# Cookie_Filter.net
KiCad netlist of a schematic drawn in EAGLE
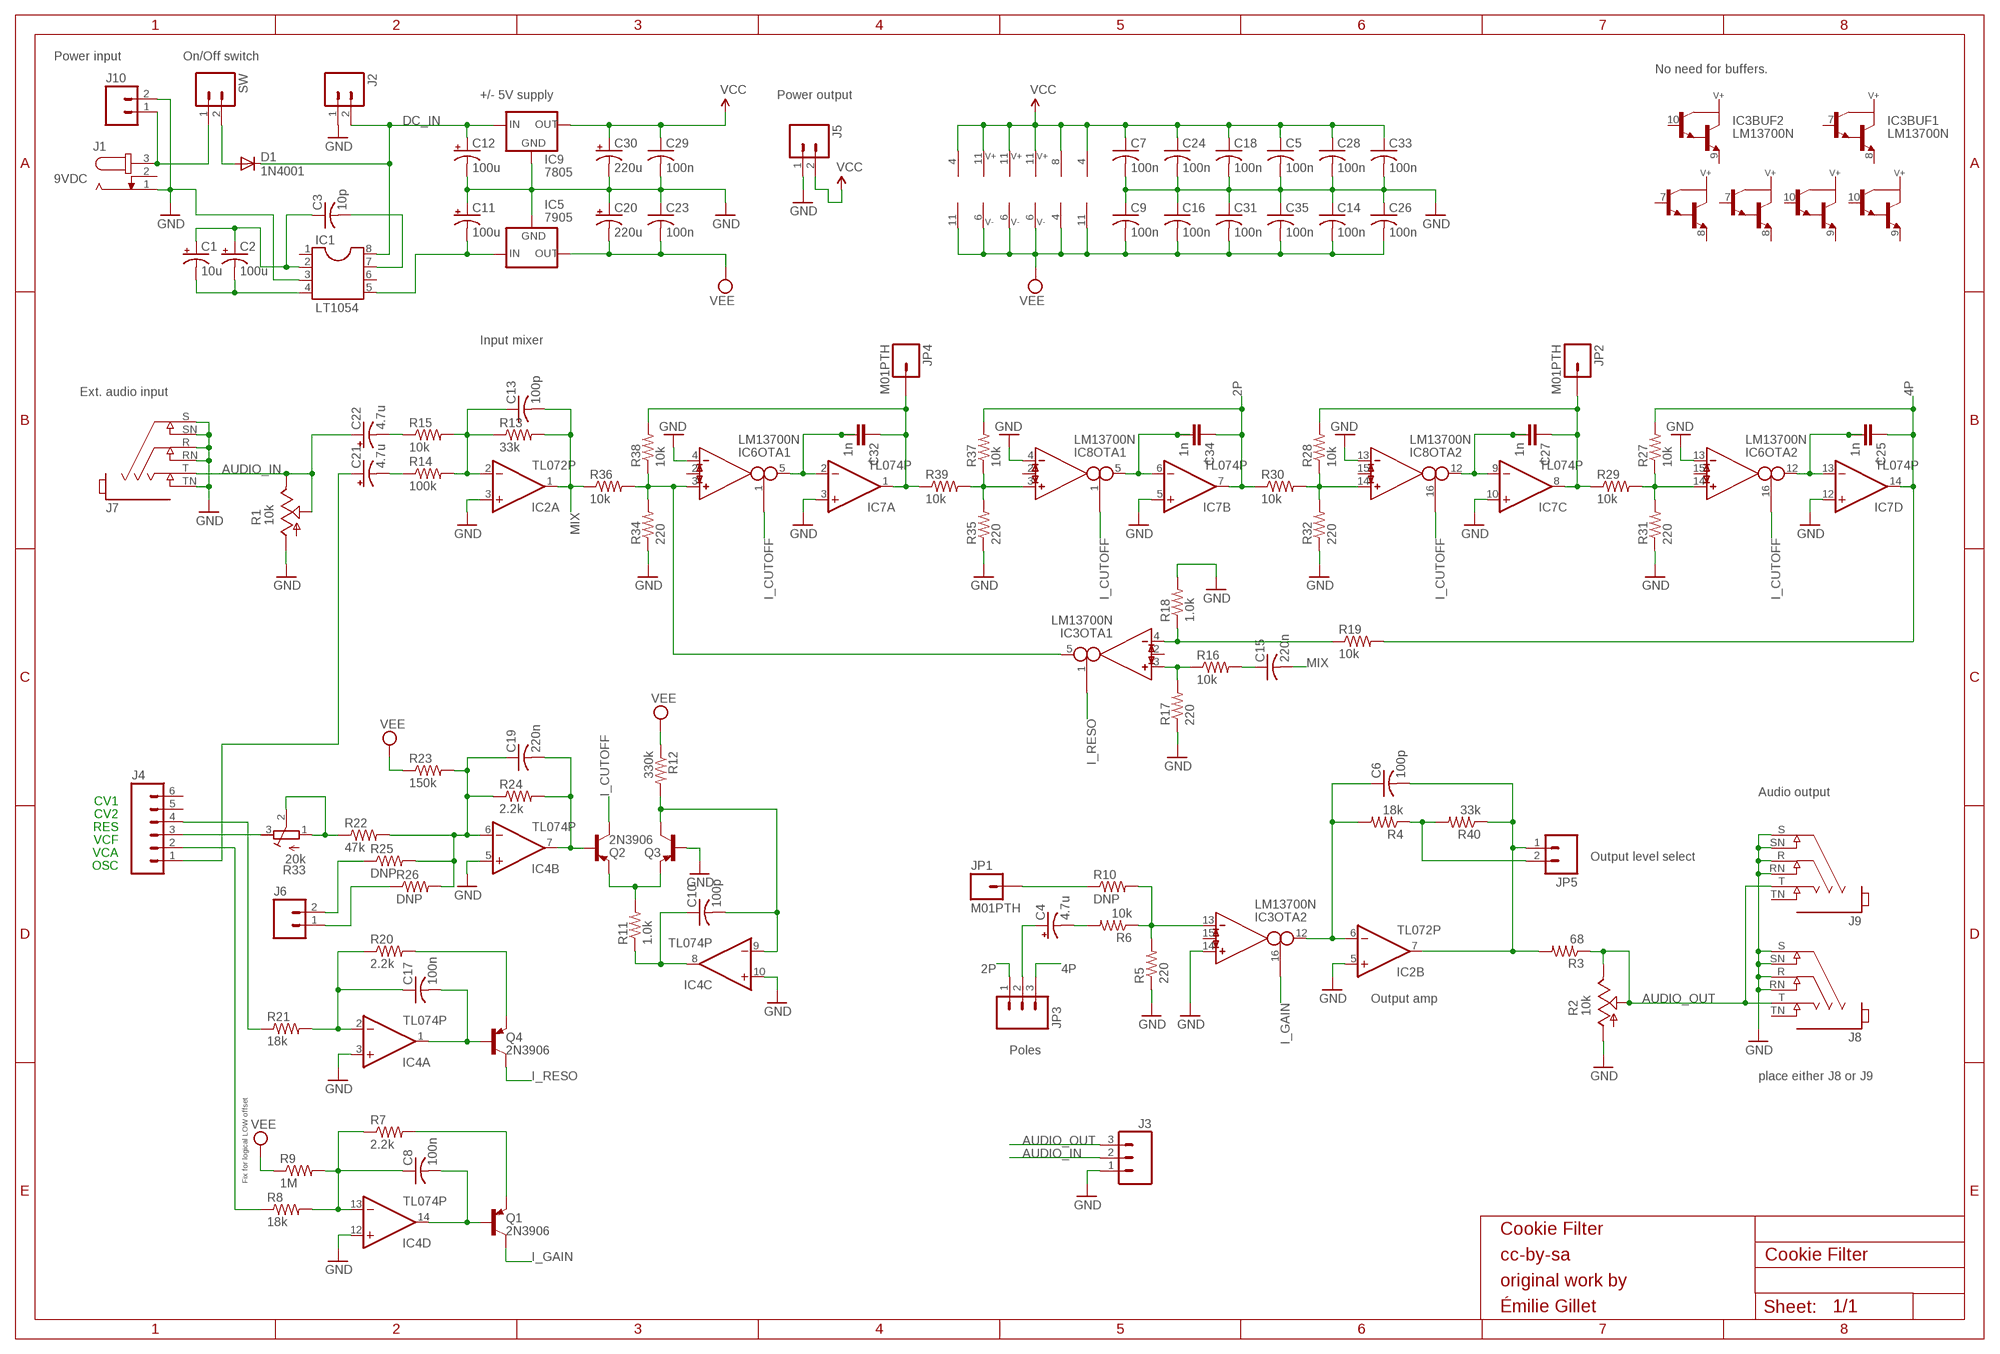
[diagram p0: schematic, sheet 1]

(export (version "E")
  (design (tool "Eeschema 10.0.6"))
  (components
    (comp (ref "C1")
      (value "10u")
      (footprint "eagle-import:E2,5-5")
      (libsource (lib "eagle-import") (part "CPOL-USE2.5-5"))
    )
    (comp (ref "C2")
      (value "100u")
      (footprint "eagle-import:E2,5-6")
      (libsource (lib "eagle-import") (part "CPOL-USE2.5-6"))
    )
    (comp (ref "C3")
      (value "10p")
      (footprint "eagle-import:C025-025X050")
      (libsource (lib "eagle-import") (part "C-US025-025X050"))
    )
    (comp (ref "C4")
      (value "4.7u")
      (footprint "eagle-import:E2,5-6")
      (libsource (lib "eagle-import") (part "CPOL-USE2.5-6"))
    )
    (comp (ref "C5")
      (value "100n")
      (footprint "eagle-import:C025-025X050")
      (libsource (lib "eagle-import") (part "C-US025-025X050"))
    )
    (comp (ref "C6")
      (value "100p")
      (footprint "eagle-import:C025-025X050")
      (libsource (lib "eagle-import") (part "C-US025-025X050"))
    )
    (comp (ref "C7")
      (value "100n")
      (footprint "eagle-import:C025-025X050")
      (libsource (lib "eagle-import") (part "C-US025-025X050"))
    )
    (comp (ref "C8")
      (value "100n")
      (footprint "eagle-import:C025-025X050")
      (libsource (lib "eagle-import") (part "C-US025-025X050"))
    )
    (comp (ref "C9")
      (value "100n")
      (footprint "eagle-import:C025-025X050")
      (libsource (lib "eagle-import") (part "C-US025-025X050"))
    )
    (comp (ref "C10")
      (value "100p")
      (footprint "eagle-import:C025-025X050")
      (libsource (lib "eagle-import") (part "C-US025-025X050"))
    )
    (comp (ref "C11")
      (value "100u")
      (footprint "eagle-import:E2,5-6")
      (libsource (lib "eagle-import") (part "CPOL-USE2.5-6"))
    )
    (comp (ref "C12")
      (value "100u")
      (footprint "eagle-import:E2,5-6")
      (libsource (lib "eagle-import") (part "CPOL-USE2.5-6"))
    )
    (comp (ref "C13")
      (value "100p")
      (footprint "eagle-import:C025-025X050")
      (libsource (lib "eagle-import") (part "C-US025-025X050"))
    )
    (comp (ref "C14")
      (value "100n")
      (footprint "eagle-import:C025-025X050")
      (libsource (lib "eagle-import") (part "C-US025-025X050"))
    )
    (comp (ref "C15")
      (value "220n")
      (footprint "eagle-import:C025-025X050")
      (libsource (lib "eagle-import") (part "C-US025-025X050"))
    )
    (comp (ref "C16")
      (value "100n")
      (footprint "eagle-import:C025-025X050")
      (libsource (lib "eagle-import") (part "C-US025-025X050"))
    )
    (comp (ref "C17")
      (value "100n")
      (footprint "eagle-import:C025-025X050")
      (libsource (lib "eagle-import") (part "C-US025-025X050"))
    )
    (comp (ref "C18")
      (value "100n")
      (footprint "eagle-import:C025-025X050")
      (libsource (lib "eagle-import") (part "C-US025-025X050"))
    )
    (comp (ref "C19")
      (value "220n")
      (footprint "eagle-import:C025-025X050")
      (libsource (lib "eagle-import") (part "C-US025-025X050"))
    )
    (comp (ref "C20")
      (value "220u")
      (footprint "eagle-import:E2,5-7")
      (libsource (lib "eagle-import") (part "CPOL-USE2.5-7"))
    )
    (comp (ref "C21")
      (value "4.7u")
      (footprint "eagle-import:E2,5-6")
      (libsource (lib "eagle-import") (part "CPOL-USE2.5-6"))
    )
    (comp (ref "C22")
      (value "4.7u")
      (footprint "eagle-import:E2,5-6")
      (libsource (lib "eagle-import") (part "CPOL-USE2.5-6"))
    )
    (comp (ref "C23")
      (value "100n")
      (footprint "eagle-import:C025-025X050")
      (libsource (lib "eagle-import") (part "C-US025-025X050"))
    )
    (comp (ref "C24")
      (value "100n")
      (footprint "eagle-import:C025-025X050")
      (libsource (lib "eagle-import") (part "C-US025-025X050"))
    )
    (comp (ref "C25")
      (value "1n")
      (footprint "eagle-import:C2.5_5-2")
      (libsource (lib "eagle-import") (part "C-2.5-5/2"))
    )
    (comp (ref "C26")
      (value "100n")
      (footprint "eagle-import:C025-025X050")
      (libsource (lib "eagle-import") (part "C-US025-025X050"))
    )
    (comp (ref "C27")
      (value "1n")
      (footprint "eagle-import:C2.5_5-2")
      (libsource (lib "eagle-import") (part "C-2.5-5/2"))
    )
    (comp (ref "C28")
      (value "100n")
      (footprint "eagle-import:C025-025X050")
      (libsource (lib "eagle-import") (part "C-US025-025X050"))
    )
    (comp (ref "C29")
      (value "100n")
      (footprint "eagle-import:C025-025X050")
      (libsource (lib "eagle-import") (part "C-US025-025X050"))
    )
    (comp (ref "C30")
      (value "220u")
      (footprint "eagle-import:E2,5-7")
      (libsource (lib "eagle-import") (part "CPOL-USE2.5-7"))
    )
    (comp (ref "C31")
      (value "100n")
      (footprint "eagle-import:C025-025X050")
      (libsource (lib "eagle-import") (part "C-US025-025X050"))
    )
    (comp (ref "C32")
      (value "1n")
      (footprint "eagle-import:C2.5_5-2")
      (libsource (lib "eagle-import") (part "C-2.5-5/2"))
    )
    (comp (ref "C33")
      (value "100n")
      (footprint "eagle-import:C025-025X050")
      (libsource (lib "eagle-import") (part "C-US025-025X050"))
    )
    (comp (ref "C34")
      (value "1n")
      (footprint "eagle-import:C2.5_5-2")
      (libsource (lib "eagle-import") (part "C-2.5-5/2"))
    )
    (comp (ref "C35")
      (value "100n")
      (footprint "eagle-import:C025-025X050")
      (libsource (lib "eagle-import") (part "C-US025-025X050"))
    )
    (comp (ref "D1")
      (value "1N4001")
      (footprint "eagle-import:DO41-10")
      (libsource (lib "eagle-import") (part "1N4004"))
    )
    (comp (ref "IC1")
      (value "LT1054")
      (footprint "eagle-import:DIL08")
      (libsource (lib "eagle-import") (part "DIL8"))
    )
    (comp (ref "IC2")
      (value "TL072P")
      (footprint "eagle-import:DIL08")
      (libsource (lib "eagle-import") (part "TL072P"))
    )
    (comp (ref "IC3")
      (value "LM13700N")
      (footprint "eagle-import:DIL16")
      (libsource (lib "eagle-import") (part "LM13700N"))
    )
    (comp (ref "IC4")
      (value "TL074P")
      (footprint "eagle-import:DIL14")
      (libsource (lib "eagle-import") (part "TL084P"))
    )
    (comp (ref "IC5")
      (value "7905")
      (footprint "eagle-import:79XXS")
      (libsource (lib "eagle-import") (part "79XXS"))
    )
    (comp (ref "IC6")
      (value "LM13700N")
      (footprint "eagle-import:DIL16")
      (libsource (lib "eagle-import") (part "LM13700N"))
    )
    (comp (ref "IC7")
      (value "TL074P")
      (footprint "eagle-import:DIL14")
      (libsource (lib "eagle-import") (part "TL084P"))
    )
    (comp (ref "IC8")
      (value "LM13700N")
      (footprint "eagle-import:DIL16")
      (libsource (lib "eagle-import") (part "LM13700N"))
    )
    (comp (ref "IC9")
      (value "7805")
      (footprint "eagle-import:78XXS")
      (libsource (lib "eagle-import") (part "78XXS"))
    )
    (comp (ref "J1")
      (value "JACK-PLUG1")
      (footprint "eagle-import:SPC4078")
      (libsource (lib "eagle-import") (part "JACK-PLUG1"))
    )
    (comp (ref "J2")
      (value "M02PTH")
      (footprint "eagle-import:1X02")
      (libsource (lib "eagle-import") (part "M02PTH"))
    )
    (comp (ref "J3")
      (value "M03PTH")
      (footprint "eagle-import:1X03")
      (libsource (lib "eagle-import") (part "M03PTH"))
    )
    (comp (ref "J4")
      (value "M06SIP")
      (footprint "eagle-import:1X06")
      (libsource (lib "eagle-import") (part "M06SIP"))
    )
    (comp (ref "J5")
      (value "M02PTH")
      (footprint "eagle-import:1X02")
      (libsource (lib "eagle-import") (part "M02PTH"))
    )
    (comp (ref "J6")
      (value "M02PTH")
      (footprint "eagle-import:1X02")
      (libsource (lib "eagle-import") (part "M02PTH"))
    )
    (comp (ref "J7")
      (value "NRJ4HF")
      (footprint "eagle-import:NRJ6HF")
      (libsource (lib "eagle-import") (part "NRJ6HF"))
    )
    (comp (ref "J8")
      (value "NRJ4HF")
      (footprint "eagle-import:NRJ6HF")
      (libsource (lib "eagle-import") (part "NRJ6HF"))
    )
    (comp (ref "J9")
      (value "NRJ4HF")
      (footprint "eagle-import:NRJ6HF")
      (libsource (lib "eagle-import") (part "NRJ6HF"))
    )
    (comp (ref "J10")
      (value "M02PTH")
      (footprint "eagle-import:1X02")
      (libsource (lib "eagle-import") (part "M02PTH"))
    )
    (comp (ref "JP1")
      (value "M01PTH")
      (footprint "eagle-import:1X01")
      (libsource (lib "eagle-import") (part "M01PTH"))
    )
    (comp (ref "JP2")
      (value "M01PTH")
      (footprint "eagle-import:1X01")
      (libsource (lib "eagle-import") (part "M01PTH"))
    )
    (comp (ref "JP3")
      (value "M03PTH")
      (footprint "eagle-import:1X03")
      (libsource (lib "eagle-import") (part "M03PTH"))
    )
    (comp (ref "JP4")
      (value "M01PTH")
      (footprint "eagle-import:1X01")
      (libsource (lib "eagle-import") (part "M01PTH"))
    )
    (comp (ref "JP5")
      (value "M02PTH")
      (footprint "eagle-import:1X02")
      (libsource (lib "eagle-import") (part "M02PTH"))
    )
    (comp (ref "Q1")
      (value "2N3906")
      (footprint "eagle-import:TO92-")
      (libsource (lib "eagle-import") (part "2N3906-"))
    )
    (comp (ref "Q2")
      (value "2N3906")
      (footprint "eagle-import:TO92-")
      (libsource (lib "eagle-import") (part "2N3906-"))
    )
    (comp (ref "Q3")
      (value "2N3906")
      (footprint "eagle-import:TO92-")
      (libsource (lib "eagle-import") (part "2N3906-"))
    )
    (comp (ref "Q4")
      (value "2N3906")
      (footprint "eagle-import:TO92-")
      (libsource (lib "eagle-import") (part "2N3906-"))
    )
    (comp (ref "R1")
      (value "10k")
      (footprint "eagle-import:CABLE_POT_6MM")
      (libsource (lib "eagle-import") (part "POT_USCABLED"))
    )
    (comp (ref "R2")
      (value "10k")
      (footprint "eagle-import:CABLE_POT_6MM")
      (libsource (lib "eagle-import") (part "POT_USCABLED"))
    )
    (comp (ref "R3")
      (value "68")
      (footprint "eagle-import:0204_7")
      (libsource (lib "eagle-import") (part "R-US_0204/7"))
    )
    (comp (ref "R4")
      (value "18k")
      (footprint "eagle-import:0204_7")
      (libsource (lib "eagle-import") (part "R-US_0204/7"))
    )
    (comp (ref "R5")
      (value "220")
      (footprint "eagle-import:0204_7")
      (libsource (lib "eagle-import") (part "R-US_0204/7"))
    )
    (comp (ref "R6")
      (value "10k")
      (footprint "eagle-import:0204_7")
      (libsource (lib "eagle-import") (part "R-US_0204/7"))
    )
    (comp (ref "R7")
      (value "2.2k")
      (footprint "eagle-import:0204_7")
      (libsource (lib "eagle-import") (part "R-US_0204/7"))
    )
    (comp (ref "R8")
      (value "18k")
      (footprint "eagle-import:0204_7")
      (libsource (lib "eagle-import") (part "R-US_0204/7"))
    )
    (comp (ref "R9")
      (value "1M")
      (footprint "eagle-import:0204_7")
      (libsource (lib "eagle-import") (part "R-US_0204/7"))
    )
    (comp (ref "R10")
      (value "DNP")
      (footprint "eagle-import:0204V")
      (libsource (lib "eagle-import") (part "R-US_0204/2V"))
    )
    (comp (ref "R11")
      (value "1.0k")
      (footprint "eagle-import:0204_7")
      (libsource (lib "eagle-import") (part "R-US_0204/7"))
    )
    (comp (ref "R12")
      (value "330k")
      (footprint "eagle-import:0204_7")
      (libsource (lib "eagle-import") (part "R-US_0204/7"))
    )
    (comp (ref "R13")
      (value "33k")
      (footprint "eagle-import:0204_7")
      (libsource (lib "eagle-import") (part "R-US_0204/7"))
    )
    (comp (ref "R14")
      (value "100k")
      (footprint "eagle-import:0204_7")
      (libsource (lib "eagle-import") (part "R-US_0204/7"))
    )
    (comp (ref "R15")
      (value "10k")
      (footprint "eagle-import:0204_7")
      (libsource (lib "eagle-import") (part "R-US_0204/7"))
    )
    (comp (ref "R16")
      (value "10k")
      (footprint "eagle-import:0204_7")
      (libsource (lib "eagle-import") (part "R-US_0204/7"))
    )
    (comp (ref "R17")
      (value "220")
      (footprint "eagle-import:0204_7")
      (libsource (lib "eagle-import") (part "R-US_0204/7"))
    )
    (comp (ref "R18")
      (value "1.0k")
      (footprint "eagle-import:0204_7")
      (libsource (lib "eagle-import") (part "R-US_0204/7"))
    )
    (comp (ref "R19")
      (value "10k")
      (footprint "eagle-import:0204_7")
      (libsource (lib "eagle-import") (part "R-US_0204/7"))
    )
    (comp (ref "R20")
      (value "2.2k")
      (footprint "eagle-import:0204_7")
      (libsource (lib "eagle-import") (part "R-US_0204/7"))
    )
    (comp (ref "R21")
      (value "18k")
      (footprint "eagle-import:0204_7")
      (libsource (lib "eagle-import") (part "R-US_0204/7"))
    )
    (comp (ref "R22")
      (value "47k")
      (footprint "eagle-import:0204_7")
      (libsource (lib "eagle-import") (part "R-US_0204/7"))
    )
    (comp (ref "R23")
      (value "150k")
      (footprint "eagle-import:0204_7")
      (libsource (lib "eagle-import") (part "R-US_0204/7"))
    )
    (comp (ref "R24")
      (value "2.2k")
      (footprint "eagle-import:0204_7")
      (libsource (lib "eagle-import") (part "R-US_0204/7"))
    )
    (comp (ref "R25")
      (value "DNP")
      (footprint "eagle-import:0204V")
      (libsource (lib "eagle-import") (part "R-US_0204/2V"))
    )
    (comp (ref "R26")
      (value "DNP")
      (footprint "eagle-import:0204V")
      (libsource (lib "eagle-import") (part "R-US_0204/2V"))
    )
    (comp (ref "R27")
      (value "10k")
      (footprint "eagle-import:0204_7")
      (libsource (lib "eagle-import") (part "R-US_0204/7"))
    )
    (comp (ref "R28")
      (value "10k")
      (footprint "eagle-import:0204_7")
      (libsource (lib "eagle-import") (part "R-US_0204/7"))
    )
    (comp (ref "R29")
      (value "10k")
      (footprint "eagle-import:0204_7")
      (libsource (lib "eagle-import") (part "R-US_0204/7"))
    )
    (comp (ref "R30")
      (value "10k")
      (footprint "eagle-import:0204_7")
      (libsource (lib "eagle-import") (part "R-US_0204/7"))
    )
    (comp (ref "R31")
      (value "220")
      (footprint "eagle-import:0204_7")
      (libsource (lib "eagle-import") (part "R-US_0204/7"))
    )
    (comp (ref "R32")
      (value "220")
      (footprint "eagle-import:0204_7")
      (libsource (lib "eagle-import") (part "R-US_0204/7"))
    )
    (comp (ref "R33")
      (value "20k")
      (footprint "eagle-import:RTRIM3296X")
      (libsource (lib "eagle-import") (part "R-TRIMM3296X"))
    )
    (comp (ref "R34")
      (value "220")
      (footprint "eagle-import:0204_7")
      (libsource (lib "eagle-import") (part "R-US_0204/7"))
    )
    (comp (ref "R35")
      (value "220")
      (footprint "eagle-import:0204_7")
      (libsource (lib "eagle-import") (part "R-US_0204/7"))
    )
    (comp (ref "R36")
      (value "10k")
      (footprint "eagle-import:0204_7")
      (libsource (lib "eagle-import") (part "R-US_0204/7"))
    )
    (comp (ref "R37")
      (value "10k")
      (footprint "eagle-import:0204_7")
      (libsource (lib "eagle-import") (part "R-US_0204/7"))
    )
    (comp (ref "R38")
      (value "10k")
      (footprint "eagle-import:0204_7")
      (libsource (lib "eagle-import") (part "R-US_0204/7"))
    )
    (comp (ref "R39")
      (value "10k")
      (footprint "eagle-import:0204_7")
      (libsource (lib "eagle-import") (part "R-US_0204/7"))
    )
    (comp (ref "R40")
      (value "33k")
      (footprint "eagle-import:0204_7")
      (libsource (lib "eagle-import") (part "R-US_0204/7"))
    )
    (comp (ref "SW")
      (value "M02PTH")
      (footprint "eagle-import:1X02")
      (libsource (lib "eagle-import") (part "M02PTH"))
    )
  )
  (nets
    (net (code "1") (name "/2P") (class "Default")
      (node (ref "C34") (pin "1") (pinfunction "1_1") (pintype "passive"))
      (node (ref "IC7") (pin "7") (pinfunction "OUT_7") (pintype "output"))
      (node (ref "JP3") (pin "1") (pinfunction "1_1") (pintype "passive"))
      (node (ref "R30") (pin "1") (pinfunction "1_1") (pintype "passive"))
      (node (ref "R37") (pin "2") (pinfunction "2_2") (pintype "passive"))
    )
    (net (code "2") (name "/4P") (class "Default")
      (node (ref "C25") (pin "1") (pinfunction "1_1") (pintype "passive"))
      (node (ref "IC7") (pin "14") (pinfunction "OUT_14") (pintype "output"))
      (node (ref "JP3") (pin "3") (pinfunction "3_3") (pintype "passive"))
      (node (ref "R19") (pin "2") (pinfunction "2_2") (pintype "passive"))
      (node (ref "R27") (pin "2") (pinfunction "2_2") (pintype "passive"))
    )
    (net (code "3") (name "/AUDIO_IN") (class "Default")
      (node (ref "C22") (pin "+") (pinfunction "+_+") (pintype "passive"))
      (node (ref "J3") (pin "2") (pinfunction "2_2") (pintype "passive"))
      (node (ref "J7") (pin "T") (pinfunction "T_T") (pintype "passive"))
      (node (ref "R1") (pin "E") (pinfunction "E_E") (pintype "passive"))
      (node (ref "R1") (pin "S") (pinfunction "S_S") (pintype "passive"))
    )
    (net (code "4") (name "/AUDIO_OUT") (class "Default")
      (node (ref "J3") (pin "3") (pinfunction "3_3") (pintype "passive"))
      (node (ref "J8") (pin "T") (pinfunction "T_T") (pintype "passive"))
      (node (ref "J9") (pin "T") (pinfunction "T_T") (pintype "passive"))
      (node (ref "R2") (pin "E") (pinfunction "E_E") (pintype "passive"))
      (node (ref "R2") (pin "S") (pinfunction "S_S") (pintype "passive"))
      (node (ref "R3") (pin "1") (pinfunction "1_1") (pintype "passive"))
    )
    (net (code "5") (name "/DC_IN") (class "Default")
      (node (ref "C12") (pin "+") (pinfunction "+_+") (pintype "passive"))
      (node (ref "D1") (pin "C") (pinfunction "C_C") (pintype "passive"))
      (node (ref "IC1") (pin "8") (pinfunction "8_8") (pintype "passive"))
      (node (ref "IC9") (pin "IN") (pinfunction "IN_IN") (pintype "input"))
      (node (ref "J2") (pin "2") (pinfunction "2_2") (pintype "passive"))
    )
    (net (code "6") (name "/I_CUTOFF") (class "Default")
      (node (ref "IC6") (pin "1") (pinfunction "I_BIAS_1") (pintype "input"))
      (node (ref "IC6") (pin "16") (pinfunction "I_BIAS_16") (pintype "input"))
      (node (ref "IC8") (pin "1") (pinfunction "I_BIAS_1") (pintype "input"))
      (node (ref "IC8") (pin "16") (pinfunction "I_BIAS_16") (pintype "input"))
      (node (ref "Q2") (pin "1") (pinfunction "C_1") (pintype "passive"))
    )
    (net (code "7") (name "/I_GAIN") (class "Default")
      (node (ref "IC3") (pin "16") (pinfunction "I_BIAS_16") (pintype "input"))
      (node (ref "Q1") (pin "1") (pinfunction "C_1") (pintype "passive"))
    )
    (net (code "8") (name "/I_RESO") (class "Default")
      (node (ref "IC3") (pin "1") (pinfunction "I_BIAS_1") (pintype "input"))
      (node (ref "Q4") (pin "1") (pinfunction "C_1") (pintype "passive"))
    )
    (net (code "9") (name "/MIX") (class "Default")
      (node (ref "C13") (pin "2") (pinfunction "2_2") (pintype "passive"))
      (node (ref "C15") (pin "2") (pinfunction "2_2") (pintype "passive"))
      (node (ref "IC2") (pin "1") (pinfunction "OUT_1") (pintype "output"))
      (node (ref "R13") (pin "2") (pinfunction "2_2") (pintype "passive"))
      (node (ref "R36") (pin "1") (pinfunction "1_1") (pintype "passive"))
    )
    (net (code "10") (name "GND") (class "Default")
      (node (ref "C11") (pin "+") (pinfunction "+_+") (pintype "passive"))
      (node (ref "C12") (pin "-") (pinfunction "-_-") (pintype "passive"))
      (node (ref "C14") (pin "1") (pinfunction "1_1") (pintype "passive"))
      (node (ref "C16") (pin "1") (pinfunction "1_1") (pintype "passive"))
      (node (ref "C18") (pin "2") (pinfunction "2_2") (pintype "passive"))
      (node (ref "C20") (pin "+") (pinfunction "+_+") (pintype "passive"))
      (node (ref "C23") (pin "1") (pinfunction "1_1") (pintype "passive"))
      (node (ref "C24") (pin "2") (pinfunction "2_2") (pintype "passive"))
      (node (ref "C26") (pin "1") (pinfunction "1_1") (pintype "passive"))
      (node (ref "C28") (pin "2") (pinfunction "2_2") (pintype "passive"))
      (node (ref "C29") (pin "2") (pinfunction "2_2") (pintype "passive"))
      (node (ref "C30") (pin "-") (pinfunction "-_-") (pintype "passive"))
      (node (ref "C31") (pin "1") (pinfunction "1_1") (pintype "passive"))
      (node (ref "C33") (pin "2") (pinfunction "2_2") (pintype "passive"))
      (node (ref "C35") (pin "1") (pinfunction "1_1") (pintype "passive"))
      (node (ref "C5") (pin "2") (pinfunction "2_2") (pintype "passive"))
      (node (ref "C7") (pin "2") (pinfunction "2_2") (pintype "passive"))
      (node (ref "C9") (pin "1") (pinfunction "1_1") (pintype "passive"))
      (node (ref "IC1") (pin "3") (pinfunction "3_3") (pintype "passive"))
      (node (ref "IC2") (pin "3") (pinfunction "+IN_3") (pintype "input"))
      (node (ref "IC2") (pin "5") (pinfunction "+IN_5") (pintype "input"))
      (node (ref "IC3") (pin "14") (pinfunction "IN_P_14") (pintype "input"))
      (node (ref "IC4") (pin "10") (pinfunction "+IN_10") (pintype "input"))
      (node (ref "IC4") (pin "12") (pinfunction "+IN_12") (pintype "input"))
      (node (ref "IC4") (pin "3") (pinfunction "+IN_3") (pintype "input"))
      (node (ref "IC4") (pin "5") (pinfunction "+IN_5") (pintype "input"))
      (node (ref "IC5") (pin "GND") (pinfunction "GND_GND") (pintype "input"))
      (node (ref "IC6") (pin "13") (pinfunction "IN_N_13") (pintype "input"))
      (node (ref "IC6") (pin "4") (pinfunction "IN_N_4") (pintype "input"))
      (node (ref "IC7") (pin "10") (pinfunction "+IN_10") (pintype "input"))
      (node (ref "IC7") (pin "12") (pinfunction "+IN_12") (pintype "input"))
      (node (ref "IC7") (pin "3") (pinfunction "+IN_3") (pintype "input"))
      (node (ref "IC7") (pin "5") (pinfunction "+IN_5") (pintype "input"))
      (node (ref "IC8") (pin "13") (pinfunction "IN_N_13") (pintype "input"))
      (node (ref "IC8") (pin "4") (pinfunction "IN_N_4") (pintype "input"))
      (node (ref "IC9") (pin "GND") (pinfunction "GND_GND") (pintype "input"))
      (node (ref "J1") (pin "1") (pinfunction "1_1") (pintype "passive"))
      (node (ref "J10") (pin "2") (pinfunction "2_2") (pintype "passive"))
      (node (ref "J2") (pin "1") (pinfunction "1_1") (pintype "passive"))
      (node (ref "J3") (pin "1") (pinfunction "1_1") (pintype "passive"))
      (node (ref "J5") (pin "1") (pinfunction "1_1") (pintype "passive"))
      (node (ref "J7") (pin "R") (pinfunction "R_R") (pintype "passive"))
      (node (ref "J7") (pin "RN") (pinfunction "RN_RN") (pintype "passive"))
      (node (ref "J7") (pin "S") (pinfunction "S_S") (pintype "passive"))
      (node (ref "J7") (pin "SN") (pinfunction "SN_SN") (pintype "passive"))
      (node (ref "J7") (pin "TN") (pinfunction "TN_TN") (pintype "passive"))
      (node (ref "J8") (pin "R") (pinfunction "R_R") (pintype "passive"))
      (node (ref "J8") (pin "RN") (pinfunction "RN_RN") (pintype "passive"))
      (node (ref "J8") (pin "S") (pinfunction "S_S") (pintype "passive"))
      (node (ref "J8") (pin "SN") (pinfunction "SN_SN") (pintype "passive"))
      (node (ref "J9") (pin "R") (pinfunction "R_R") (pintype "passive"))
      (node (ref "J9") (pin "RN") (pinfunction "RN_RN") (pintype "passive"))
      (node (ref "J9") (pin "S") (pinfunction "S_S") (pintype "passive"))
      (node (ref "J9") (pin "SN") (pinfunction "SN_SN") (pintype "passive"))
      (node (ref "Q3") (pin "2") (pinfunction "B_2") (pintype "passive"))
      (node (ref "R1") (pin "A") (pinfunction "A_A") (pintype "passive"))
      (node (ref "R17") (pin "1") (pinfunction "1_1") (pintype "passive"))
      (node (ref "R18") (pin "2") (pinfunction "2_2") (pintype "passive"))
      (node (ref "R2") (pin "A") (pinfunction "A_A") (pintype "passive"))
      (node (ref "R31") (pin "1") (pinfunction "1_1") (pintype "passive"))
      (node (ref "R32") (pin "1") (pinfunction "1_1") (pintype "passive"))
      (node (ref "R34") (pin "1") (pinfunction "1_1") (pintype "passive"))
      (node (ref "R35") (pin "1") (pinfunction "1_1") (pintype "passive"))
      (node (ref "R5") (pin "1") (pinfunction "1_1") (pintype "passive"))
    )
    (net (code "11") (name "Net-(C1-Pad+)") (class "Default")
      (node (ref "C1") (pin "+") (pinfunction "+_+") (pintype "passive"))
      (node (ref "C2") (pin "+") (pinfunction "+_+") (pintype "passive"))
      (node (ref "C3") (pin "1") (pinfunction "1_1") (pintype "passive"))
      (node (ref "IC1") (pin "2") (pinfunction "2_2") (pintype "passive"))
    )
    (net (code "12") (name "Net-(C1-Pad-)") (class "Default")
      (node (ref "C1") (pin "-") (pinfunction "-_-") (pintype "passive"))
      (node (ref "C2") (pin "-") (pinfunction "-_-") (pintype "passive"))
      (node (ref "IC1") (pin "4") (pinfunction "4_4") (pintype "passive"))
    )
    (net (code "13") (name "Net-(C3-Pad2)") (class "Default")
      (node (ref "C3") (pin "2") (pinfunction "2_2") (pintype "passive"))
      (node (ref "IC1") (pin "7") (pinfunction "7_7") (pintype "passive"))
    )
    (net (code "14") (name "Net-(C4-Pad+)") (class "Default")
      (node (ref "C4") (pin "+") (pinfunction "+_+") (pintype "passive"))
      (node (ref "JP3") (pin "2") (pinfunction "2_2") (pintype "passive"))
    )
    (net (code "15") (name "Net-(C4-Pad-)") (class "Default")
      (node (ref "C4") (pin "-") (pinfunction "-_-") (pintype "passive"))
      (node (ref "R6") (pin "2") (pinfunction "2_2") (pintype "passive"))
    )
    (net (code "16") (name "Net-(C11-Pad-)") (class "Default")
      (node (ref "C11") (pin "-") (pinfunction "-_-") (pintype "passive"))
      (node (ref "IC1") (pin "5") (pinfunction "5_5") (pintype "passive"))
      (node (ref "IC5") (pin "IN") (pinfunction "IN_IN") (pintype "input"))
    )
    (net (code "17") (name "Net-(C15-Pad1)") (class "Default")
      (node (ref "C15") (pin "1") (pinfunction "1_1") (pintype "passive"))
      (node (ref "R16") (pin "2") (pinfunction "2_2") (pintype "passive"))
    )
    (net (code "18") (name "Net-(C21-Pad+)") (class "Default")
      (node (ref "C21") (pin "+") (pinfunction "+_+") (pintype "passive"))
      (node (ref "J4") (pin "1") (pinfunction "1_1") (pintype "passive"))
    )
    (net (code "19") (name "Net-(C21-Pad-)") (class "Default")
      (node (ref "C21") (pin "-") (pinfunction "-_-") (pintype "passive"))
      (node (ref "R14") (pin "1") (pinfunction "1_1") (pintype "passive"))
    )
    (net (code "20") (name "Net-(C22-Pad-)") (class "Default")
      (node (ref "C22") (pin "-") (pinfunction "-_-") (pintype "passive"))
      (node (ref "R15") (pin "1") (pinfunction "1_1") (pintype "passive"))
    )
    (net (code "21") (name "Net-(D1-PadA)") (class "Default")
      (node (ref "D1") (pin "A") (pinfunction "A_A") (pintype "passive"))
      (node (ref "SW") (pin "2") (pinfunction "2_2") (pintype "passive"))
    )
    (net (code "22") (name "Net-(IC2A--IN)") (class "Default")
      (node (ref "C13") (pin "1") (pinfunction "1_1") (pintype "passive"))
      (node (ref "IC2") (pin "2") (pinfunction "-IN_2") (pintype "input"))
      (node (ref "R13") (pin "1") (pinfunction "1_1") (pintype "passive"))
      (node (ref "R14") (pin "2") (pinfunction "2_2") (pintype "passive"))
      (node (ref "R15") (pin "2") (pinfunction "2_2") (pintype "passive"))
    )
    (net (code "23") (name "Net-(IC2B--IN)") (class "Default")
      (node (ref "C6") (pin "1") (pinfunction "1_1") (pintype "passive"))
      (node (ref "IC2") (pin "6") (pinfunction "-IN_6") (pintype "input"))
      (node (ref "IC3") (pin "12") (pinfunction "OUT_12") (pintype "output"))
      (node (ref "R4") (pin "2") (pinfunction "2_2") (pintype "passive"))
    )
    (net (code "24") (name "Net-(IC2B-OUT)") (class "Default")
      (node (ref "C6") (pin "2") (pinfunction "2_2") (pintype "passive"))
      (node (ref "IC2") (pin "7") (pinfunction "OUT_7") (pintype "output"))
      (node (ref "JP5") (pin "1") (pinfunction "1_1") (pintype "passive"))
      (node (ref "R3") (pin "2") (pinfunction "2_2") (pintype "passive"))
      (node (ref "R40") (pin "1") (pinfunction "1_1") (pintype "passive"))
    )
    (net (code "25") (name "Net-(IC3C-IN_N)") (class "Default")
      (node (ref "IC3") (pin "4") (pinfunction "IN_N_4") (pintype "input"))
      (node (ref "R18") (pin "1") (pinfunction "1_1") (pintype "passive"))
      (node (ref "R19") (pin "1") (pinfunction "1_1") (pintype "passive"))
    )
    (net (code "26") (name "Net-(IC3C-IN_P)") (class "Default")
      (node (ref "IC3") (pin "3") (pinfunction "IN_P_3") (pintype "input"))
      (node (ref "R16") (pin "1") (pinfunction "1_1") (pintype "passive"))
      (node (ref "R17") (pin "2") (pinfunction "2_2") (pintype "passive"))
    )
    (net (code "27") (name "Net-(IC3C-OUT)") (class "Default")
      (node (ref "IC3") (pin "5") (pinfunction "OUT_5") (pintype "output"))
      (node (ref "IC6") (pin "3") (pinfunction "IN_P_3") (pintype "input"))
      (node (ref "R34") (pin "2") (pinfunction "2_2") (pintype "passive"))
      (node (ref "R36") (pin "2") (pinfunction "2_2") (pintype "passive"))
      (node (ref "R38") (pin "1") (pinfunction "1_1") (pintype "passive"))
    )
    (net (code "28") (name "Net-(IC3D-IN_N)") (class "Default")
      (node (ref "IC3") (pin "13") (pinfunction "IN_N_13") (pintype "input"))
      (node (ref "R10") (pin "2") (pinfunction "2_2") (pintype "passive"))
      (node (ref "R5") (pin "2") (pinfunction "2_2") (pintype "passive"))
      (node (ref "R6") (pin "1") (pinfunction "1_1") (pintype "passive"))
    )
    (net (code "29") (name "Net-(IC4A--IN)") (class "Default")
      (node (ref "C17") (pin "1") (pinfunction "1_1") (pintype "passive"))
      (node (ref "IC4") (pin "2") (pinfunction "-IN_2") (pintype "input"))
      (node (ref "R20") (pin "1") (pinfunction "1_1") (pintype "passive"))
      (node (ref "R21") (pin "2") (pinfunction "2_2") (pintype "passive"))
    )
    (net (code "30") (name "Net-(IC4A-OUT)") (class "Default")
      (node (ref "C17") (pin "2") (pinfunction "2_2") (pintype "passive"))
      (node (ref "IC4") (pin "1") (pinfunction "OUT_1") (pintype "output"))
      (node (ref "Q4") (pin "2") (pinfunction "B_2") (pintype "passive"))
    )
    (net (code "31") (name "Net-(IC4B--IN)") (class "Default")
      (node (ref "C19") (pin "1") (pinfunction "1_1") (pintype "passive"))
      (node (ref "IC4") (pin "6") (pinfunction "-IN_6") (pintype "input"))
      (node (ref "R22") (pin "2") (pinfunction "2_2") (pintype "passive"))
      (node (ref "R23") (pin "2") (pinfunction "2_2") (pintype "passive"))
      (node (ref "R24") (pin "1") (pinfunction "1_1") (pintype "passive"))
      (node (ref "R25") (pin "2") (pinfunction "2_2") (pintype "passive"))
      (node (ref "R26") (pin "2") (pinfunction "2_2") (pintype "passive"))
    )
    (net (code "32") (name "Net-(IC4B-OUT)") (class "Default")
      (node (ref "C19") (pin "2") (pinfunction "2_2") (pintype "passive"))
      (node (ref "IC4") (pin "7") (pinfunction "OUT_7") (pintype "output"))
      (node (ref "Q2") (pin "2") (pinfunction "B_2") (pintype "passive"))
      (node (ref "R24") (pin "2") (pinfunction "2_2") (pintype "passive"))
    )
    (net (code "33") (name "Net-(IC4C--IN)") (class "Default")
      (node (ref "C10") (pin "2") (pinfunction "2_2") (pintype "passive"))
      (node (ref "IC4") (pin "9") (pinfunction "-IN_9") (pintype "input"))
      (node (ref "Q3") (pin "1") (pinfunction "C_1") (pintype "passive"))
      (node (ref "R12") (pin "2") (pinfunction "2_2") (pintype "passive"))
    )
    (net (code "34") (name "Net-(IC4C-OUT)") (class "Default")
      (node (ref "C10") (pin "1") (pinfunction "1_1") (pintype "passive"))
      (node (ref "IC4") (pin "8") (pinfunction "OUT_8") (pintype "output"))
      (node (ref "R11") (pin "1") (pinfunction "1_1") (pintype "passive"))
    )
    (net (code "35") (name "Net-(IC4D--IN)") (class "Default")
      (node (ref "C8") (pin "1") (pinfunction "1_1") (pintype "passive"))
      (node (ref "IC4") (pin "13") (pinfunction "-IN_13") (pintype "input"))
      (node (ref "R7") (pin "1") (pinfunction "1_1") (pintype "passive"))
      (node (ref "R8") (pin "2") (pinfunction "2_2") (pintype "passive"))
      (node (ref "R9") (pin "2") (pinfunction "2_2") (pintype "passive"))
    )
    (net (code "36") (name "Net-(IC4D-OUT)") (class "Default")
      (node (ref "C8") (pin "2") (pinfunction "2_2") (pintype "passive"))
      (node (ref "IC4") (pin "14") (pinfunction "OUT_14") (pintype "output"))
      (node (ref "Q1") (pin "2") (pinfunction "B_2") (pintype "passive"))
    )
    (net (code "37") (name "Net-(IC6C-OUT)") (class "Default")
      (node (ref "C32") (pin "2") (pinfunction "2_2") (pintype "passive"))
      (node (ref "C32") (pin "3") (pinfunction "3_3") (pintype "passive"))
      (node (ref "IC6") (pin "5") (pinfunction "OUT_5") (pintype "output"))
      (node (ref "IC7") (pin "2") (pinfunction "-IN_2") (pintype "input"))
    )
    (net (code "38") (name "Net-(IC6D-IN_P)") (class "Default")
      (node (ref "IC6") (pin "14") (pinfunction "IN_P_14") (pintype "input"))
      (node (ref "R27") (pin "1") (pinfunction "1_1") (pintype "passive"))
      (node (ref "R29") (pin "2") (pinfunction "2_2") (pintype "passive"))
      (node (ref "R31") (pin "2") (pinfunction "2_2") (pintype "passive"))
    )
    (net (code "39") (name "Net-(IC6D-OUT)") (class "Default")
      (node (ref "C25") (pin "2") (pinfunction "2_2") (pintype "passive"))
      (node (ref "C25") (pin "3") (pinfunction "3_3") (pintype "passive"))
      (node (ref "IC6") (pin "12") (pinfunction "OUT_12") (pintype "output"))
      (node (ref "IC7") (pin "13") (pinfunction "-IN_13") (pintype "input"))
    )
    (net (code "40") (name "Net-(IC7A-OUT)") (class "Default")
      (node (ref "C32") (pin "1") (pinfunction "1_1") (pintype "passive"))
      (node (ref "IC7") (pin "1") (pinfunction "OUT_1") (pintype "output"))
      (node (ref "JP4") (pin "1") (pinfunction "1_1") (pintype "passive"))
      (node (ref "R38") (pin "2") (pinfunction "2_2") (pintype "passive"))
      (node (ref "R39") (pin "1") (pinfunction "1_1") (pintype "passive"))
    )
    (net (code "41") (name "Net-(IC7B--IN)") (class "Default")
      (node (ref "C34") (pin "2") (pinfunction "2_2") (pintype "passive"))
      (node (ref "C34") (pin "3") (pinfunction "3_3") (pintype "passive"))
      (node (ref "IC7") (pin "6") (pinfunction "-IN_6") (pintype "input"))
      (node (ref "IC8") (pin "5") (pinfunction "OUT_5") (pintype "output"))
    )
    (net (code "42") (name "Net-(IC7C--IN)") (class "Default")
      (node (ref "C27") (pin "2") (pinfunction "2_2") (pintype "passive"))
      (node (ref "C27") (pin "3") (pinfunction "3_3") (pintype "passive"))
      (node (ref "IC7") (pin "9") (pinfunction "-IN_9") (pintype "input"))
      (node (ref "IC8") (pin "12") (pinfunction "OUT_12") (pintype "output"))
    )
    (net (code "43") (name "Net-(IC7C-OUT)") (class "Default")
      (node (ref "C27") (pin "1") (pinfunction "1_1") (pintype "passive"))
      (node (ref "IC7") (pin "8") (pinfunction "OUT_8") (pintype "output"))
      (node (ref "JP2") (pin "1") (pinfunction "1_1") (pintype "passive"))
      (node (ref "R28") (pin "2") (pinfunction "2_2") (pintype "passive"))
      (node (ref "R29") (pin "1") (pinfunction "1_1") (pintype "passive"))
    )
    (net (code "44") (name "Net-(IC8C-IN_P)") (class "Default")
      (node (ref "IC8") (pin "3") (pinfunction "IN_P_3") (pintype "input"))
      (node (ref "R35") (pin "2") (pinfunction "2_2") (pintype "passive"))
      (node (ref "R37") (pin "1") (pinfunction "1_1") (pintype "passive"))
      (node (ref "R39") (pin "2") (pinfunction "2_2") (pintype "passive"))
    )
    (net (code "45") (name "Net-(IC8D-IN_P)") (class "Default")
      (node (ref "IC8") (pin "14") (pinfunction "IN_P_14") (pintype "input"))
      (node (ref "R28") (pin "1") (pinfunction "1_1") (pintype "passive"))
      (node (ref "R30") (pin "2") (pinfunction "2_2") (pintype "passive"))
      (node (ref "R32") (pin "2") (pinfunction "2_2") (pintype "passive"))
    )
    (net (code "46") (name "Net-(J1-Pad3)") (class "Default")
      (node (ref "J1") (pin "3") (pinfunction "3_3") (pintype "passive"))
      (node (ref "J10") (pin "1") (pinfunction "1_1") (pintype "passive"))
      (node (ref "SW") (pin "1") (pinfunction "1_1") (pintype "passive"))
    )
    (net (code "47") (name "Net-(J4-Pad2)") (class "Default")
      (node (ref "J4") (pin "2") (pinfunction "2_2") (pintype "passive"))
      (node (ref "R8") (pin "1") (pinfunction "1_1") (pintype "passive"))
    )
    (net (code "48") (name "Net-(J4-Pad4)") (class "Default")
      (node (ref "J4") (pin "4") (pinfunction "4_4") (pintype "passive"))
      (node (ref "R21") (pin "1") (pinfunction "1_1") (pintype "passive"))
    )
    (net (code "49") (name "Net-(J6-Pad1)") (class "Default")
      (node (ref "J6") (pin "1") (pinfunction "1_1") (pintype "passive"))
      (node (ref "R26") (pin "1") (pinfunction "1_1") (pintype "passive"))
    )
    (net (code "50") (name "Net-(J6-Pad2)") (class "Default")
      (node (ref "J6") (pin "2") (pinfunction "2_2") (pintype "passive"))
      (node (ref "R25") (pin "1") (pinfunction "1_1") (pintype "passive"))
    )
    (net (code "51") (name "Net-(JP1-Pad1)") (class "Default")
      (node (ref "JP1") (pin "1") (pinfunction "1_1") (pintype "passive"))
      (node (ref "R10") (pin "1") (pinfunction "1_1") (pintype "passive"))
    )
    (net (code "52") (name "Net-(JP5-Pad2)") (class "Default")
      (node (ref "JP5") (pin "2") (pinfunction "2_2") (pintype "passive"))
      (node (ref "R4") (pin "1") (pinfunction "1_1") (pintype "passive"))
      (node (ref "R40") (pin "2") (pinfunction "2_2") (pintype "passive"))
    )
    (net (code "53") (name "Net-(Q1-E)") (class "Default")
      (node (ref "Q1") (pin "3") (pinfunction "E_3") (pintype "passive"))
      (node (ref "R7") (pin "2") (pinfunction "2_2") (pintype "passive"))
    )
    (net (code "54") (name "Net-(Q2-E)") (class "Default")
      (node (ref "Q2") (pin "3") (pinfunction "E_3") (pintype "passive"))
      (node (ref "Q3") (pin "3") (pinfunction "E_3") (pintype "passive"))
      (node (ref "R11") (pin "2") (pinfunction "2_2") (pintype "passive"))
    )
    (net (code "55") (name "Net-(Q4-E)") (class "Default")
      (node (ref "Q4") (pin "3") (pinfunction "E_3") (pintype "passive"))
      (node (ref "R20") (pin "2") (pinfunction "2_2") (pintype "passive"))
    )
    (net (code "56") (name "Net-(R33-A)") (class "Default")
      (node (ref "J4") (pin "3") (pinfunction "3_3") (pintype "passive"))
      (node (ref "R33") (pin "3") (pinfunction "A_3") (pintype "passive"))
    )
    (net (code "57") (name "Net-(R33-E)") (class "Default")
      (node (ref "R22") (pin "1") (pinfunction "1_1") (pintype "passive"))
      (node (ref "R33") (pin "1") (pinfunction "E_1") (pintype "passive"))
      (node (ref "R33") (pin "2") (pinfunction "S_2") (pintype "passive"))
    )
    (net (code "58") (name "VCC") (class "Default")
      (node (ref "C18") (pin "1") (pinfunction "1_1") (pintype "passive"))
      (node (ref "C24") (pin "1") (pinfunction "1_1") (pintype "passive"))
      (node (ref "C28") (pin "1") (pinfunction "1_1") (pintype "passive"))
      (node (ref "C29") (pin "1") (pinfunction "1_1") (pintype "passive"))
      (node (ref "C30") (pin "+") (pinfunction "+_+") (pintype "passive"))
      (node (ref "C33") (pin "1") (pinfunction "1_1") (pintype "passive"))
      (node (ref "C5") (pin "1") (pinfunction "1_1") (pintype "passive"))
      (node (ref "C7") (pin "1") (pinfunction "1_1") (pintype "passive"))
      (node (ref "IC2") (pin "8") (pinfunction "V+_8") (pintype "power_in"))
      (node (ref "IC3") (pin "11") (pinfunction "V+_11") (pintype "power_in"))
      (node (ref "IC4") (pin "4") (pinfunction "V+_4") (pintype "power_in"))
      (node (ref "IC6") (pin "11") (pinfunction "V+_11") (pintype "power_in"))
      (node (ref "IC7") (pin "4") (pinfunction "V+_4") (pintype "power_in"))
      (node (ref "IC8") (pin "11") (pinfunction "V+_11") (pintype "power_in"))
      (node (ref "IC9") (pin "OUT") (pinfunction "OUT_OUT") (pintype "passive"))
      (node (ref "J5") (pin "2") (pinfunction "2_2") (pintype "passive"))
    )
    (net (code "59") (name "VEE") (class "Default")
      (node (ref "C14") (pin "2") (pinfunction "2_2") (pintype "passive"))
      (node (ref "C16") (pin "2") (pinfunction "2_2") (pintype "passive"))
      (node (ref "C20") (pin "-") (pinfunction "-_-") (pintype "passive"))
      (node (ref "C23") (pin "2") (pinfunction "2_2") (pintype "passive"))
      (node (ref "C26") (pin "2") (pinfunction "2_2") (pintype "passive"))
      (node (ref "C31") (pin "2") (pinfunction "2_2") (pintype "passive"))
      (node (ref "C35") (pin "2") (pinfunction "2_2") (pintype "passive"))
      (node (ref "C9") (pin "2") (pinfunction "2_2") (pintype "passive"))
      (node (ref "IC2") (pin "4") (pinfunction "V-_4") (pintype "power_in"))
      (node (ref "IC3") (pin "6") (pinfunction "V-_6") (pintype "power_in"))
      (node (ref "IC4") (pin "11") (pinfunction "V-_11") (pintype "power_in"))
      (node (ref "IC5") (pin "OUT") (pinfunction "OUT_OUT") (pintype "passive"))
      (node (ref "IC6") (pin "6") (pinfunction "V-_6") (pintype "power_in"))
      (node (ref "IC7") (pin "11") (pinfunction "V-_11") (pintype "power_in"))
      (node (ref "IC8") (pin "6") (pinfunction "V-_6") (pintype "power_in"))
      (node (ref "R12") (pin "1") (pinfunction "1_1") (pintype "passive"))
      (node (ref "R23") (pin "1") (pinfunction "1_1") (pintype "passive"))
      (node (ref "R9") (pin "1") (pinfunction "1_1") (pintype "passive"))
    )
    (net (code "60") (name "unconnected-(IC1-Pad1)") (class "Default")
      (node (ref "IC1") (pin "1") (pinfunction "1_1") (pintype "passive"))
    )
    (net (code "61") (name "unconnected-(IC1-Pad6)") (class "Default")
      (node (ref "IC1") (pin "6") (pinfunction "6_6") (pintype "passive"))
    )
    (net (code "62") (name "unconnected-(IC3A-B-Pad7)") (class "Default")
      (node (ref "IC3") (pin "7") (pinfunction "B_7") (pintype "passive"))
    )
    (net (code "63") (name "unconnected-(IC3A-E-Pad8)") (class "Default")
      (node (ref "IC3") (pin "8") (pinfunction "E_8") (pintype "passive"))
    )
    (net (code "64") (name "unconnected-(IC3B-B-Pad10)") (class "Default")
      (node (ref "IC3") (pin "10") (pinfunction "B_10") (pintype "passive"))
    )
    (net (code "65") (name "unconnected-(IC3B-E-Pad9)") (class "Default")
      (node (ref "IC3") (pin "9") (pinfunction "E_9") (pintype "passive"))
    )
    (net (code "66") (name "unconnected-(IC3C-I_DIODE-Pad2)") (class "Default")
      (node (ref "IC3") (pin "2") (pinfunction "I_DIODE_2") (pintype "input"))
    )
    (net (code "67") (name "unconnected-(IC3D-I_DIODE-Pad15)") (class "Default")
      (node (ref "IC3") (pin "15") (pinfunction "I_DIODE_15") (pintype "input"))
    )
    (net (code "68") (name "unconnected-(IC6A-B-Pad7)") (class "Default")
      (node (ref "IC6") (pin "7") (pinfunction "B_7") (pintype "passive"))
    )
    (net (code "69") (name "unconnected-(IC6A-E-Pad8)") (class "Default")
      (node (ref "IC6") (pin "8") (pinfunction "E_8") (pintype "passive"))
    )
    (net (code "70") (name "unconnected-(IC6B-B-Pad10)") (class "Default")
      (node (ref "IC6") (pin "10") (pinfunction "B_10") (pintype "passive"))
    )
    (net (code "71") (name "unconnected-(IC6B-E-Pad9)") (class "Default")
      (node (ref "IC6") (pin "9") (pinfunction "E_9") (pintype "passive"))
    )
    (net (code "72") (name "unconnected-(IC6C-I_DIODE-Pad2)") (class "Default")
      (node (ref "IC6") (pin "2") (pinfunction "I_DIODE_2") (pintype "input"))
    )
    (net (code "73") (name "unconnected-(IC6D-I_DIODE-Pad15)") (class "Default")
      (node (ref "IC6") (pin "15") (pinfunction "I_DIODE_15") (pintype "input"))
    )
    (net (code "74") (name "unconnected-(IC8A-B-Pad7)") (class "Default")
      (node (ref "IC8") (pin "7") (pinfunction "B_7") (pintype "passive"))
    )
    (net (code "75") (name "unconnected-(IC8A-E-Pad8)") (class "Default")
      (node (ref "IC8") (pin "8") (pinfunction "E_8") (pintype "passive"))
    )
    (net (code "76") (name "unconnected-(IC8B-B-Pad10)") (class "Default")
      (node (ref "IC8") (pin "10") (pinfunction "B_10") (pintype "passive"))
    )
    (net (code "77") (name "unconnected-(IC8B-E-Pad9)") (class "Default")
      (node (ref "IC8") (pin "9") (pinfunction "E_9") (pintype "passive"))
    )
    (net (code "78") (name "unconnected-(IC8C-I_DIODE-Pad2)") (class "Default")
      (node (ref "IC8") (pin "2") (pinfunction "I_DIODE_2") (pintype "input"))
    )
    (net (code "79") (name "unconnected-(IC8D-I_DIODE-Pad15)") (class "Default")
      (node (ref "IC8") (pin "15") (pinfunction "I_DIODE_15") (pintype "input"))
    )
    (net (code "80") (name "unconnected-(J1-Pad2)") (class "Default")
      (node (ref "J1") (pin "2") (pinfunction "2_2") (pintype "passive"))
    )
    (net (code "81") (name "unconnected-(J4-Pad5)") (class "Default")
      (node (ref "J4") (pin "5") (pinfunction "5_5") (pintype "passive"))
    )
    (net (code "82") (name "unconnected-(J4-Pad6)") (class "Default")
      (node (ref "J4") (pin "6") (pinfunction "6_6") (pintype "passive"))
    )
    (net (code "83") (name "unconnected-(J8-PadTN)") (class "Default")
      (node (ref "J8") (pin "TN") (pinfunction "TN_TN") (pintype "passive"))
    )
    (net (code "84") (name "unconnected-(J9-PadTN)") (class "Default")
      (node (ref "J9") (pin "TN") (pinfunction "TN_TN") (pintype "passive"))
    )
  )
)
